# multiboard.net
KiCad netlist of a schematic drawn in EAGLE
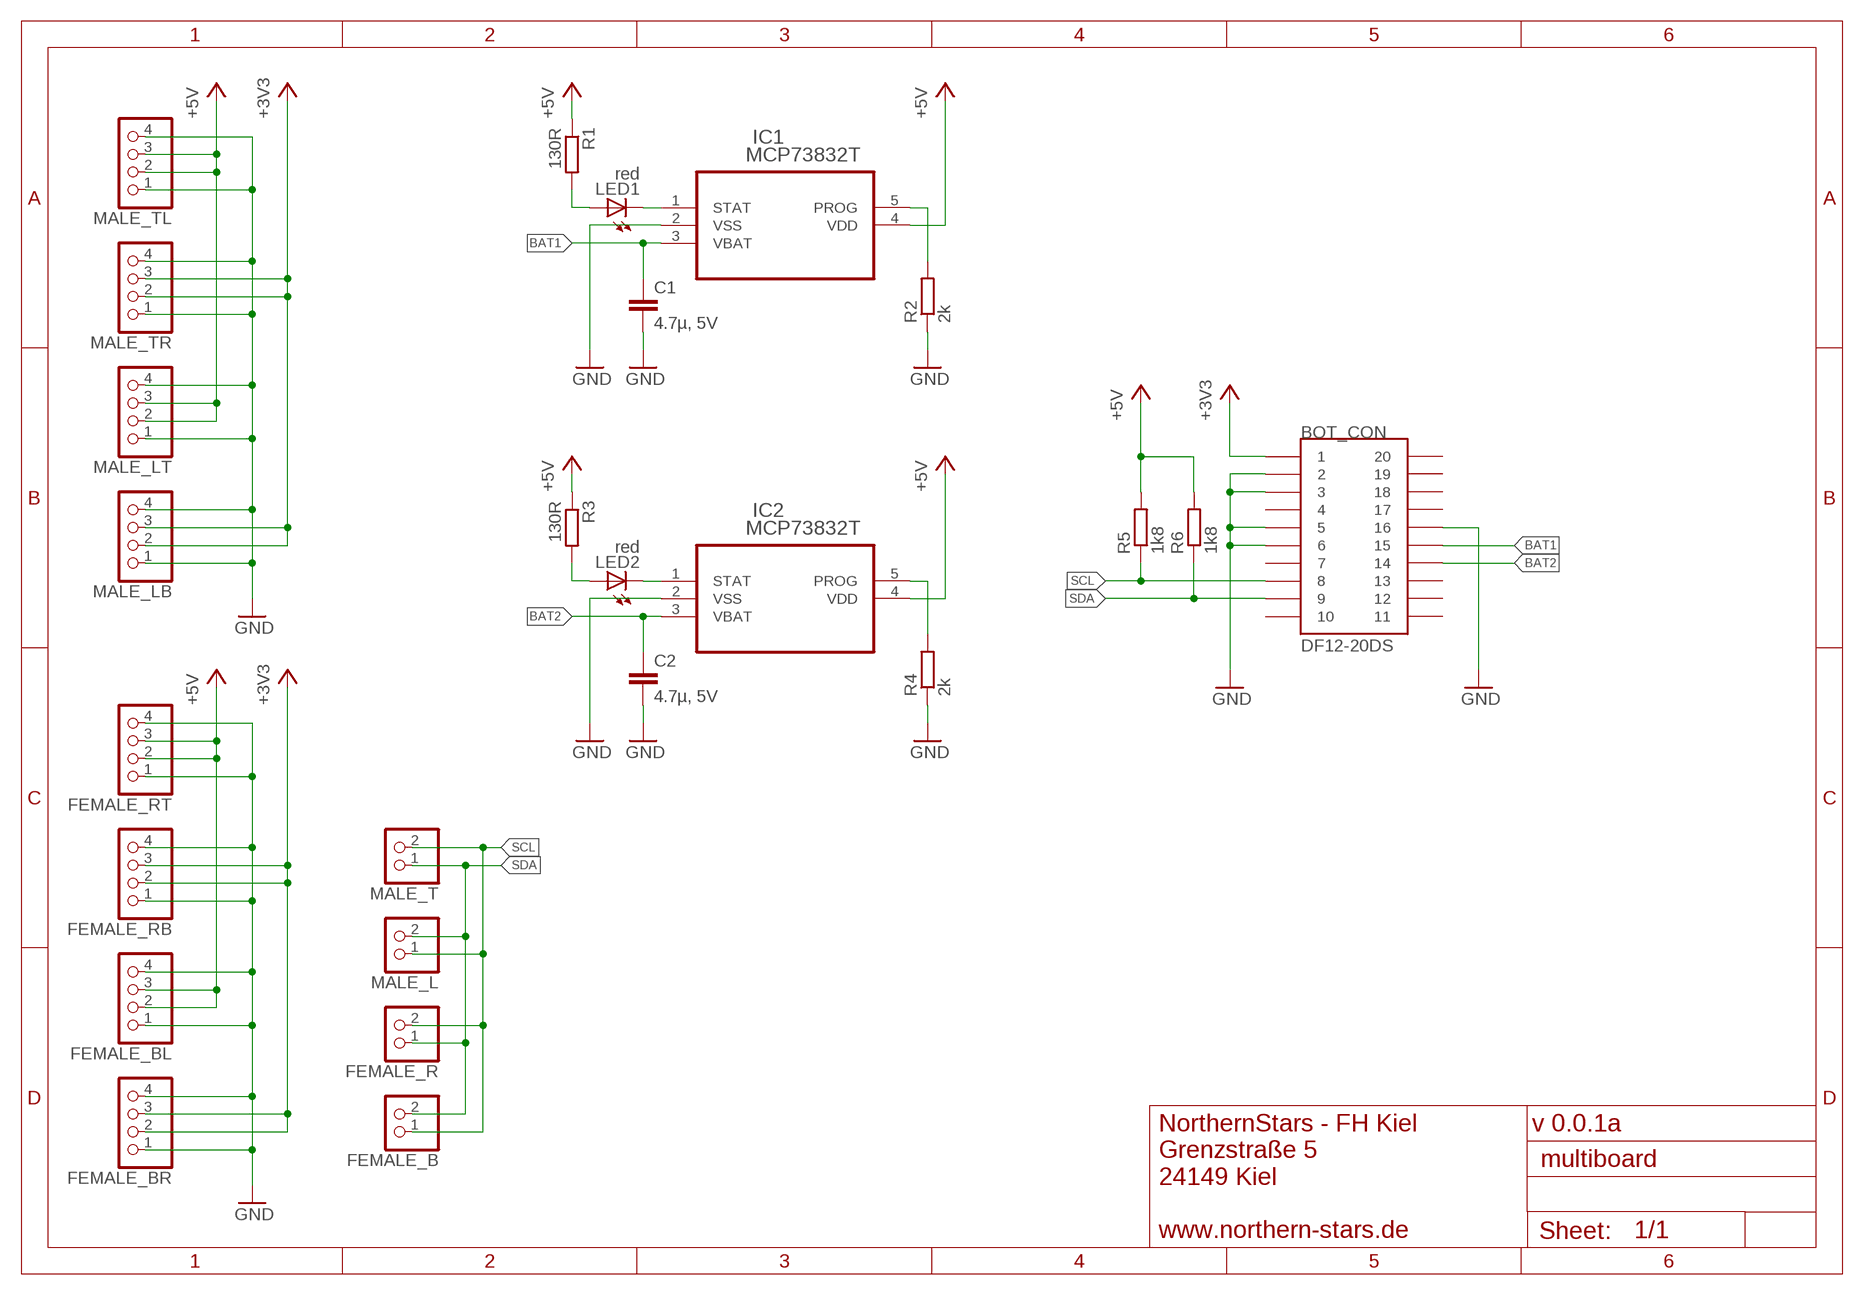
[diagram p0: schematic, sheet 1]

(export (version "E")
  (design (tool "Eeschema 10.0.6"))
  (components
    (comp (ref "BOT_CON")
      (value "DF12-20DS")
      (footprint "eagle-import:DF12-20DS")
      (libsource (lib "eagle-import") (part "DF12-20DS"))
    )
    (comp (ref "C1")
      (value "4.7µ, 5V")
      (footprint "eagle-import:C1206")
      (libsource (lib "eagle-import") (part "C-EUC1206"))
    )
    (comp (ref "C2")
      (value "4.7µ, 5V")
      (footprint "eagle-import:C1206")
      (libsource (lib "eagle-import") (part "C-EUC1206"))
    )
    (comp (ref "FEMALE_B")
      (value "PINHD-1X02_2.54-SMD-90°")
      (footprint "eagle-import:1X02SMD_90")
      (libsource (lib "eagle-import") (part "PINHD-1X02_2.54-SMD-90°"))
    )
    (comp (ref "FEMALE_BL")
      (value "PINHD-1X04_2.54-SMD-90°")
      (footprint "eagle-import:1X04SMD_90")
      (libsource (lib "eagle-import") (part "PINHD-1X04_2.54-SMD-90°"))
    )
    (comp (ref "FEMALE_BR")
      (value "PINHD-1X04_2.54-SMD-90°")
      (footprint "eagle-import:1X04SMD_90")
      (libsource (lib "eagle-import") (part "PINHD-1X04_2.54-SMD-90°"))
    )
    (comp (ref "FEMALE_R")
      (value "PINHD-1X02_2.54-SMD-90°")
      (footprint "eagle-import:1X02SMD_90")
      (libsource (lib "eagle-import") (part "PINHD-1X02_2.54-SMD-90°"))
    )
    (comp (ref "FEMALE_RB")
      (value "PINHD-1X04_2.54-SMD-90°")
      (footprint "eagle-import:1X04SMD_90")
      (libsource (lib "eagle-import") (part "PINHD-1X04_2.54-SMD-90°"))
    )
    (comp (ref "FEMALE_RT")
      (value "PINHD-1X04_2.54-SMD-90°")
      (footprint "eagle-import:1X04SMD_90")
      (libsource (lib "eagle-import") (part "PINHD-1X04_2.54-SMD-90°"))
    )
    (comp (ref "IC1")
      (value "MCP73832T")
      (footprint "eagle-import:SOT95P300X145-5N")
      (fields (field (name "MPN") "MCP73832T-2DCI/OT"))
      (libsource (lib "eagle-import") (part "MCP73832T-2DCI/OT"))
    )
    (comp (ref "IC2")
      (value "MCP73832T")
      (footprint "eagle-import:SOT95P300X145-5N")
      (fields (field (name "MPN") "MCP73832T-2DCI/OT"))
      (libsource (lib "eagle-import") (part "MCP73832T-2DCI/OT"))
    )
    (comp (ref "LED1")
      (value "red")
      (footprint "eagle-import:CHIPLED_1206")
      (libsource (lib "eagle-import") (part "LEDCHIPLED_1206"))
    )
    (comp (ref "LED2")
      (value "red")
      (footprint "eagle-import:CHIPLED_1206")
      (libsource (lib "eagle-import") (part "LEDCHIPLED_1206"))
    )
    (comp (ref "MALE_L")
      (value "PINHD-1X02_2.54-SMD-90°")
      (footprint "eagle-import:1X02SMD_90")
      (libsource (lib "eagle-import") (part "PINHD-1X02_2.54-SMD-90°"))
    )
    (comp (ref "MALE_LB")
      (value "PINHD-1X04_2.54-SMD-90°")
      (footprint "eagle-import:1X04SMD_90")
      (libsource (lib "eagle-import") (part "PINHD-1X04_2.54-SMD-90°"))
    )
    (comp (ref "MALE_LT")
      (value "PINHD-1X04_2.54-SMD-90°")
      (footprint "eagle-import:1X04SMD_90")
      (libsource (lib "eagle-import") (part "PINHD-1X04_2.54-SMD-90°"))
    )
    (comp (ref "MALE_T")
      (value "PINHD-1X02_2.54-SMD-90°")
      (footprint "eagle-import:1X02SMD_90")
      (libsource (lib "eagle-import") (part "PINHD-1X02_2.54-SMD-90°"))
    )
    (comp (ref "MALE_TL")
      (value "PINHD-1X04_2.54-SMD-90°")
      (footprint "eagle-import:1X04SMD_90")
      (libsource (lib "eagle-import") (part "PINHD-1X04_2.54-SMD-90°"))
    )
    (comp (ref "MALE_TR")
      (value "PINHD-1X04_2.54-SMD-90°")
      (footprint "eagle-import:1X04SMD_90")
      (libsource (lib "eagle-import") (part "PINHD-1X04_2.54-SMD-90°"))
    )
    (comp (ref "R1")
      (value "130R")
      (footprint "eagle-import:R1206")
      (libsource (lib "eagle-import") (part "R-EU_R1206"))
    )
    (comp (ref "R2")
      (value "2k")
      (footprint "eagle-import:R1206")
      (libsource (lib "eagle-import") (part "R-EU_R1206"))
    )
    (comp (ref "R3")
      (value "130R")
      (footprint "eagle-import:R1206")
      (libsource (lib "eagle-import") (part "R-EU_R1206"))
    )
    (comp (ref "R4")
      (value "2k")
      (footprint "eagle-import:R1206")
      (libsource (lib "eagle-import") (part "R-EU_R1206"))
    )
    (comp (ref "R5")
      (value "1k8")
      (footprint "eagle-import:R1206")
      (libsource (lib "eagle-import") (part "R-EU_R1206"))
    )
    (comp (ref "R6")
      (value "1k8")
      (footprint "eagle-import:R1206")
      (libsource (lib "eagle-import") (part "R-EU_R1206"))
    )
  )
  (nets
    (net (code "1") (name "+3V3") (class "Default")
      (node (ref "BOT_CON") (pin "1") (pinfunction "1_1") (pintype "bidirectional"))
      (node (ref "FEMALE_BR") (pin "2") (pinfunction "2_2") (pintype "passive"))
      (node (ref "FEMALE_BR") (pin "3") (pinfunction "3_3") (pintype "passive"))
      (node (ref "FEMALE_RB") (pin "2") (pinfunction "2_2") (pintype "passive"))
      (node (ref "FEMALE_RB") (pin "3") (pinfunction "3_3") (pintype "passive"))
      (node (ref "MALE_LB") (pin "2") (pinfunction "2_2") (pintype "passive"))
      (node (ref "MALE_LB") (pin "3") (pinfunction "3_3") (pintype "passive"))
      (node (ref "MALE_TR") (pin "2") (pinfunction "2_2") (pintype "passive"))
      (node (ref "MALE_TR") (pin "3") (pinfunction "3_3") (pintype "passive"))
    )
    (net (code "2") (name "+5V") (class "Default")
      (node (ref "FEMALE_BL") (pin "2") (pinfunction "2_2") (pintype "passive"))
      (node (ref "FEMALE_BL") (pin "3") (pinfunction "3_3") (pintype "passive"))
      (node (ref "FEMALE_RT") (pin "2") (pinfunction "2_2") (pintype "passive"))
      (node (ref "FEMALE_RT") (pin "3") (pinfunction "3_3") (pintype "passive"))
      (node (ref "IC1") (pin "4") (pinfunction "VDD_4") (pintype "power_in"))
      (node (ref "IC2") (pin "4") (pinfunction "VDD_4") (pintype "power_in"))
      (node (ref "MALE_LT") (pin "2") (pinfunction "2_2") (pintype "passive"))
      (node (ref "MALE_LT") (pin "3") (pinfunction "3_3") (pintype "passive"))
      (node (ref "MALE_TL") (pin "2") (pinfunction "2_2") (pintype "passive"))
      (node (ref "MALE_TL") (pin "3") (pinfunction "3_3") (pintype "passive"))
      (node (ref "R1") (pin "1") (pinfunction "1_1") (pintype "passive"))
      (node (ref "R3") (pin "1") (pinfunction "1_1") (pintype "passive"))
      (node (ref "R5") (pin "2") (pinfunction "2_2") (pintype "passive"))
      (node (ref "R6") (pin "2") (pinfunction "2_2") (pintype "passive"))
    )
    (net (code "3") (name "BAT1") (class "Default")
      (node (ref "BOT_CON") (pin "15") (pinfunction "15_15") (pintype "bidirectional"))
      (node (ref "C1") (pin "1") (pinfunction "1_1") (pintype "passive"))
      (node (ref "IC1") (pin "3") (pinfunction "VBAT_3") (pintype "input"))
    )
    (net (code "4") (name "BAT2") (class "Default")
      (node (ref "BOT_CON") (pin "14") (pinfunction "14_14") (pintype "bidirectional"))
      (node (ref "C2") (pin "1") (pinfunction "1_1") (pintype "passive"))
      (node (ref "IC2") (pin "3") (pinfunction "VBAT_3") (pintype "input"))
    )
    (net (code "5") (name "GND") (class "Default")
      (node (ref "BOT_CON") (pin "16") (pinfunction "16_16") (pintype "bidirectional"))
      (node (ref "BOT_CON") (pin "2") (pinfunction "2_2") (pintype "bidirectional"))
      (node (ref "BOT_CON") (pin "3") (pinfunction "3_3") (pintype "bidirectional"))
      (node (ref "BOT_CON") (pin "5") (pinfunction "5_5") (pintype "bidirectional"))
      (node (ref "BOT_CON") (pin "6") (pinfunction "6_6") (pintype "bidirectional"))
      (node (ref "C1") (pin "2") (pinfunction "2_2") (pintype "passive"))
      (node (ref "C2") (pin "2") (pinfunction "2_2") (pintype "passive"))
      (node (ref "FEMALE_BL") (pin "1") (pinfunction "1_1") (pintype "passive"))
      (node (ref "FEMALE_BL") (pin "4") (pinfunction "4_4") (pintype "passive"))
      (node (ref "FEMALE_BR") (pin "1") (pinfunction "1_1") (pintype "passive"))
      (node (ref "FEMALE_BR") (pin "4") (pinfunction "4_4") (pintype "passive"))
      (node (ref "FEMALE_RB") (pin "1") (pinfunction "1_1") (pintype "passive"))
      (node (ref "FEMALE_RB") (pin "4") (pinfunction "4_4") (pintype "passive"))
      (node (ref "FEMALE_RT") (pin "1") (pinfunction "1_1") (pintype "passive"))
      (node (ref "FEMALE_RT") (pin "4") (pinfunction "4_4") (pintype "passive"))
      (node (ref "IC1") (pin "2") (pinfunction "VSS_2") (pintype "passive"))
      (node (ref "IC2") (pin "2") (pinfunction "VSS_2") (pintype "passive"))
      (node (ref "MALE_LB") (pin "1") (pinfunction "1_1") (pintype "passive"))
      (node (ref "MALE_LB") (pin "4") (pinfunction "4_4") (pintype "passive"))
      (node (ref "MALE_LT") (pin "1") (pinfunction "1_1") (pintype "passive"))
      (node (ref "MALE_LT") (pin "4") (pinfunction "4_4") (pintype "passive"))
      (node (ref "MALE_TL") (pin "1") (pinfunction "1_1") (pintype "passive"))
      (node (ref "MALE_TL") (pin "4") (pinfunction "4_4") (pintype "passive"))
      (node (ref "MALE_TR") (pin "1") (pinfunction "1_1") (pintype "passive"))
      (node (ref "MALE_TR") (pin "4") (pinfunction "4_4") (pintype "passive"))
      (node (ref "R2") (pin "1") (pinfunction "1_1") (pintype "passive"))
      (node (ref "R4") (pin "1") (pinfunction "1_1") (pintype "passive"))
    )
    (net (code "6") (name "Net-(IC1-PROG)") (class "Default")
      (node (ref "IC1") (pin "5") (pinfunction "PROG_5") (pintype "input"))
      (node (ref "R2") (pin "2") (pinfunction "2_2") (pintype "passive"))
    )
    (net (code "7") (name "Net-(IC1-STAT)") (class "Default")
      (node (ref "IC1") (pin "1") (pinfunction "STAT_1") (pintype "input"))
      (node (ref "LED1") (pin "C") (pinfunction "C_C") (pintype "passive"))
    )
    (net (code "8") (name "Net-(IC2-PROG)") (class "Default")
      (node (ref "IC2") (pin "5") (pinfunction "PROG_5") (pintype "input"))
      (node (ref "R4") (pin "2") (pinfunction "2_2") (pintype "passive"))
    )
    (net (code "9") (name "Net-(IC2-STAT)") (class "Default")
      (node (ref "IC2") (pin "1") (pinfunction "STAT_1") (pintype "input"))
      (node (ref "LED2") (pin "C") (pinfunction "C_C") (pintype "passive"))
    )
    (net (code "10") (name "Net-(LED1-PadA)") (class "Default")
      (node (ref "LED1") (pin "A") (pinfunction "A_A") (pintype "passive"))
      (node (ref "R1") (pin "2") (pinfunction "2_2") (pintype "passive"))
    )
    (net (code "11") (name "Net-(LED2-PadA)") (class "Default")
      (node (ref "LED2") (pin "A") (pinfunction "A_A") (pintype "passive"))
      (node (ref "R3") (pin "2") (pinfunction "2_2") (pintype "passive"))
    )
    (net (code "12") (name "SCL") (class "Default")
      (node (ref "BOT_CON") (pin "8") (pinfunction "8_8") (pintype "bidirectional"))
      (node (ref "FEMALE_B") (pin "1") (pinfunction "1_1") (pintype "passive"))
      (node (ref "FEMALE_R") (pin "2") (pinfunction "2_2") (pintype "passive"))
      (node (ref "MALE_L") (pin "1") (pinfunction "1_1") (pintype "passive"))
      (node (ref "MALE_T") (pin "2") (pinfunction "2_2") (pintype "passive"))
      (node (ref "R5") (pin "1") (pinfunction "1_1") (pintype "passive"))
    )
    (net (code "13") (name "SDA") (class "Default")
      (node (ref "BOT_CON") (pin "9") (pinfunction "9_9") (pintype "bidirectional"))
      (node (ref "FEMALE_B") (pin "2") (pinfunction "2_2") (pintype "passive"))
      (node (ref "FEMALE_R") (pin "1") (pinfunction "1_1") (pintype "passive"))
      (node (ref "MALE_L") (pin "2") (pinfunction "2_2") (pintype "passive"))
      (node (ref "MALE_T") (pin "1") (pinfunction "1_1") (pintype "passive"))
      (node (ref "R6") (pin "1") (pinfunction "1_1") (pintype "passive"))
    )
    (net (code "14") (name "unconnected-(BOT_CON-Pad4)") (class "Default")
      (node (ref "BOT_CON") (pin "4") (pinfunction "4_4") (pintype "bidirectional"))
    )
    (net (code "15") (name "unconnected-(BOT_CON-Pad7)") (class "Default")
      (node (ref "BOT_CON") (pin "7") (pinfunction "7_7") (pintype "bidirectional"))
    )
    (net (code "16") (name "unconnected-(BOT_CON-Pad10)") (class "Default")
      (node (ref "BOT_CON") (pin "10") (pinfunction "10_10") (pintype "bidirectional"))
    )
    (net (code "17") (name "unconnected-(BOT_CON-Pad11)") (class "Default")
      (node (ref "BOT_CON") (pin "11") (pinfunction "11_11") (pintype "bidirectional"))
    )
    (net (code "18") (name "unconnected-(BOT_CON-Pad12)") (class "Default")
      (node (ref "BOT_CON") (pin "12") (pinfunction "12_12") (pintype "bidirectional"))
    )
    (net (code "19") (name "unconnected-(BOT_CON-Pad13)") (class "Default")
      (node (ref "BOT_CON") (pin "13") (pinfunction "13_13") (pintype "bidirectional"))
    )
    (net (code "20") (name "unconnected-(BOT_CON-Pad17)") (class "Default")
      (node (ref "BOT_CON") (pin "17") (pinfunction "17_17") (pintype "bidirectional"))
    )
    (net (code "21") (name "unconnected-(BOT_CON-Pad18)") (class "Default")
      (node (ref "BOT_CON") (pin "18") (pinfunction "18_18") (pintype "bidirectional"))
    )
    (net (code "22") (name "unconnected-(BOT_CON-Pad19)") (class "Default")
      (node (ref "BOT_CON") (pin "19") (pinfunction "19_19") (pintype "bidirectional"))
    )
    (net (code "23") (name "unconnected-(BOT_CON-Pad20)") (class "Default")
      (node (ref "BOT_CON") (pin "20") (pinfunction "20_20") (pintype "bidirectional"))
    )
  )
)
